# MCU.net
KiCad netlist of a schematic drawn in Altium Designer
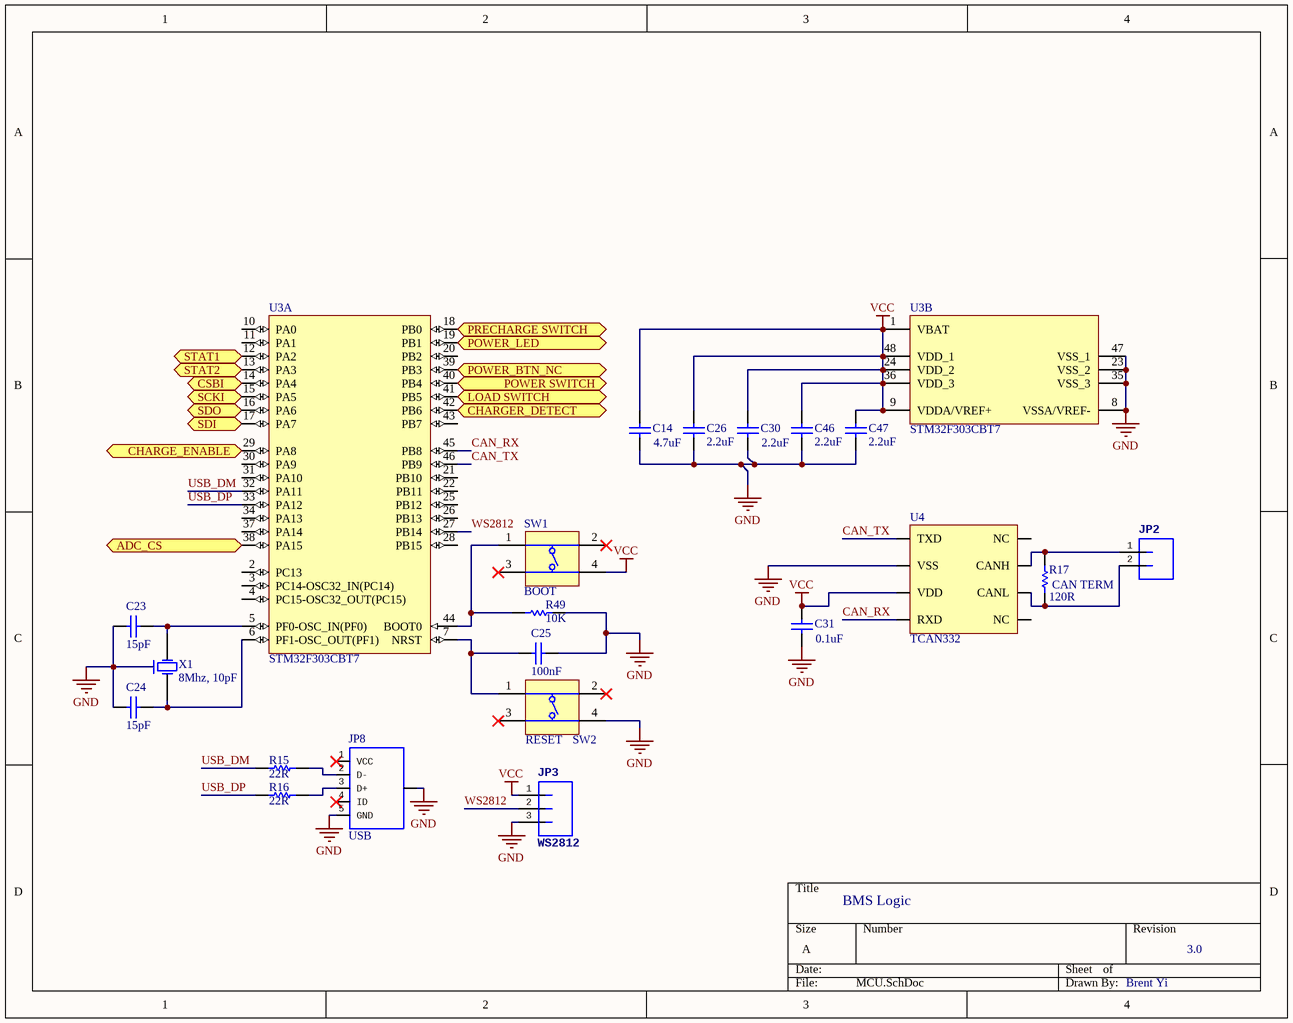
[diagram p0: MCU.SchDoc]

(export (version "E")
  (design (tool "Eeschema 10.0.6"))
  (components
    (comp (ref "C14")
      (value "4.7uF")
      (footprint "CAPC0603(1608)55_N")
      (description "CAP 2.2uF 16V Â±10% 0603 (1608 Metric) Thickness 0.55mm SMD")
      (fields (field (name "TOLERANCE") "Â±10%"))
      (libsource (lib "Altium Content Vault") (part "CMP-1035-02762-1"))
    )
    (comp (ref "C23")
      (value "15pF")
      (footprint "CAPC0603(1608)55_N")
      (description "CAP 2.2uF 16V Â±10% 0603 (1608 Metric) Thickness 0.55mm SMD")
      (fields (field (name "TOLERANCE") "Â±10%"))
      (libsource (lib "Altium Content Vault") (part "CMP-1035-02762-1"))
    )
    (comp (ref "C24")
      (value "15pF")
      (footprint "CAPC0603(1608)55_N")
      (description "CAP 2.2uF 16V Â±10% 0603 (1608 Metric) Thickness 0.55mm SMD")
      (fields (field (name "TOLERANCE") "Â±10%"))
      (libsource (lib "Altium Content Vault") (part "CMP-1035-02762-1"))
    )
    (comp (ref "C25")
      (value "100nF")
      (footprint "CAPC0603(1608)55_N")
      (description "CAP 2.2uF 16V Â±10% 0603 (1608 Metric) Thickness 0.55mm SMD")
      (fields (field (name "TOLERANCE") "Â±10%"))
      (libsource (lib "Altium Content Vault") (part "CMP-1035-02762-1"))
    )
    (comp (ref "C26")
      (value "2.2uF")
      (footprint "CAPC0603(1608)55_N")
      (description "CAP 2.2uF 16V Â±10% 0603 (1608 Metric) Thickness 0.55mm SMD")
      (fields (field (name "TOLERANCE") "Â±10%"))
      (libsource (lib "Altium Content Vault") (part "CMP-1035-02762-1"))
    )
    (comp (ref "C30")
      (value "2.2uF")
      (footprint "CAPC0603(1608)55_N")
      (description "CAP 2.2uF 16V Â±10% 0603 (1608 Metric) Thickness 0.55mm SMD")
      (fields (field (name "TOLERANCE") "Â±10%"))
      (libsource (lib "Altium Content Vault") (part "CMP-1035-02762-1"))
    )
    (comp (ref "C31")
      (value "0.1uF")
      (footprint "CAPC0603(1608)55_N")
      (description "CAP 2.2uF 16V Â±10% 0603 (1608 Metric) Thickness 0.55mm SMD")
      (fields (field (name "TOLERANCE") "Â±10%"))
      (libsource (lib "Altium Content Vault") (part "CMP-1035-02762-1"))
    )
    (comp (ref "C46")
      (value "2.2uF")
      (footprint "CAPC0603(1608)55_N")
      (description "CAP 2.2uF 16V Â±10% 0603 (1608 Metric) Thickness 0.55mm SMD")
      (fields (field (name "TOLERANCE") "Â±10%"))
      (libsource (lib "Altium Content Vault") (part "CMP-1035-02762-1"))
    )
    (comp (ref "C47")
      (value "2.2uF")
      (footprint "CAPC0603(1608)55_N")
      (description "CAP 2.2uF 16V Â±10% 0603 (1608 Metric) Thickness 0.55mm SMD")
      (fields (field (name "TOLERANCE") "Â±10%"))
      (libsource (lib "Altium Content Vault") (part "CMP-1035-02762-1"))
    )
    (comp (ref "JP2")
      (value "~")
      (footprint "JST-2-PTH-VERT")
      (libsource (lib "Components") (part "JST_2_VERT"))
    )
    (comp (ref "JP3")
      (value "WS2812")
      (footprint "JST-3-PTH-VERT")
      (libsource (lib "Components") (part "JST_3"))
    )
    (comp (ref "JP8")
      (value "USB")
      (footprint "USB-MICROB")
      (libsource (lib "Components") (part "USB_MICROB_PLUG-SMT"))
    )
    (comp (ref "R15")
      (value "22R")
      (footprint "RESC0603(1608)_N")
      (description "100R 0.1W 5% 0603 (1608 Metric)  SMD")
      (fields (field (name "TOLERANCE") "5 %") (field (name "POWER") "0.1 W"))
      (libsource (lib "Altium Content Vault") (part "CMP-1012-00050-1"))
    )
    (comp (ref "R16")
      (value "22R")
      (footprint "RESC0603(1608)_N")
      (description "100R 0.1W 5% 0603 (1608 Metric)  SMD")
      (fields (field (name "TOLERANCE") "5 %") (field (name "POWER") "0.1 W"))
      (libsource (lib "Altium Content Vault") (part "CMP-1012-00050-1"))
    )
    (comp (ref "R17")
      (value "CAN TERM")
      (footprint "RESC0603(1608)_N")
      (description "100R 0.1W 5% 0603 (1608 Metric)  SMD")
      (fields
        (field (name "TOLERANCE") "5 %")
        (field (name "ALTIUM_VALUE") "120R")
        (field (name "POWER") "0.1 W")
      )
      (libsource (lib "Altium Content Vault") (part "CMP-1012-00050-1"))
    )
    (comp (ref "R49")
      (value "10K")
      (footprint "RESC0603(1608)_N")
      (description "100R 0.1W 5% 0603 (1608 Metric)  SMD")
      (fields (field (name "TOLERANCE") "5 %") (field (name "POWER") "0.1 W"))
      (libsource (lib "Altium Content Vault") (part "CMP-1012-00050-1"))
    )
    (comp (ref "SW1")
      (value "BOOT")
      (footprint "SWITCH")
      (description "Switch, SPNO Push Button SMD")
      (fields (field (name "MANUFACTURER") "Diptronics") (field (name "PARTNUMBER") "DTSM-61NT/R"))
      (libsource (lib "altium-import") (part "root_0_DIPT-DTSM-6_"))
    )
    (comp (ref "SW2")
      (value "RESET")
      (footprint "SWITCH")
      (description "Switch, SPNO Push Button SMD")
      (fields (field (name "MANUFACTURER") "Diptronics") (field (name "PARTNUMBER") "DTSM-61NT/R"))
      (libsource (lib "altium-import") (part "root_0_DIPT-DTSM-6_"))
    )
    (comp (ref "U3")
      (value "STM32F303CBT7")
      (footprint "STM-LQFP48_L")
      (libsource (lib "Altium Content Vault") (part "MC-ARM-STM32F303-SQ48"))
    )
    (comp (ref "U4")
      (value "TCAN332")
      (footprint "SOT65P280X145-6N")
      (libsource (lib "Components") (part "TCAN332"))
    )
    (comp (ref "X1")
      (value "8Mhz, 10pF")
      (footprint "ABRA-ABM3B-4_V")
      (libsource (lib "Components") (part "ABRA-ABM3B-4"))
    )
  )
  (nets
    (net (code "1") (name "/ADC_CS") (class "Default")
      (node (ref "U3") (pin "38") (pinfunction "PA15_38") (pintype "bidirectional"))
    )
    (net (code "2") (name "/CAN_RX") (class "Default")
      (node (ref "U3") (pin "45") (pinfunction "PB8_45") (pintype "bidirectional"))
      (node (ref "U4") (pin "4") (pinfunction "RXD_4") (pintype "passive"))
    )
    (net (code "3") (name "/CAN_TX") (class "Default")
      (node (ref "U3") (pin "46") (pinfunction "PB9_46") (pintype "bidirectional"))
      (node (ref "U4") (pin "1") (pinfunction "TXD_1") (pintype "passive"))
    )
    (net (code "4") (name "/CHARGER_DETECT") (class "Default")
      (node (ref "U3") (pin "42") (pinfunction "PB6_42") (pintype "bidirectional"))
    )
    (net (code "5") (name "/CHARGE_ENABLE") (class "Default")
      (node (ref "U3") (pin "29") (pinfunction "PA8_29") (pintype "bidirectional"))
    )
    (net (code "6") (name "/CSBI") (class "Default")
      (node (ref "U3") (pin "14") (pinfunction "PA4_14") (pintype "bidirectional"))
    )
    (net (code "7") (name "/LOAD SWITCH") (class "Default")
      (node (ref "U3") (pin "41") (pinfunction "PB5_41") (pintype "bidirectional"))
    )
    (net (code "8") (name "/POWER SWITCH") (class "Default")
      (node (ref "U3") (pin "40") (pinfunction "PB4_40") (pintype "bidirectional"))
    )
    (net (code "9") (name "/POWER_BTN_NC") (class "Default")
      (node (ref "U3") (pin "39") (pinfunction "PB3_39") (pintype "bidirectional"))
    )
    (net (code "10") (name "/POWER_LED") (class "Default")
      (node (ref "U3") (pin "19") (pinfunction "PB1_19") (pintype "bidirectional"))
    )
    (net (code "11") (name "/PRECHARGE SWITCH") (class "Default")
      (node (ref "U3") (pin "18") (pinfunction "PB0_18") (pintype "bidirectional"))
    )
    (net (code "12") (name "/SCKI") (class "Default")
      (node (ref "U3") (pin "15") (pinfunction "PA5_15") (pintype "bidirectional"))
    )
    (net (code "13") (name "/SDI") (class "Default")
      (node (ref "U3") (pin "17") (pinfunction "PA7_17") (pintype "bidirectional"))
    )
    (net (code "14") (name "/SDO") (class "Default")
      (node (ref "U3") (pin "16") (pinfunction "PA6_16") (pintype "bidirectional"))
    )
    (net (code "15") (name "/STAT1") (class "Default")
      (node (ref "U3") (pin "12") (pinfunction "PA2_12") (pintype "bidirectional"))
    )
    (net (code "16") (name "/STAT2") (class "Default")
      (node (ref "U3") (pin "13") (pinfunction "PA3_13") (pintype "bidirectional"))
    )
    (net (code "17") (name "/USB_DM") (class "Default")
      (node (ref "R15") (pin "1") (pinfunction "1_1") (pintype "passive"))
      (node (ref "U3") (pin "32") (pinfunction "PA11_32") (pintype "bidirectional"))
    )
    (net (code "18") (name "/USB_DP") (class "Default")
      (node (ref "R16") (pin "1") (pinfunction "1_1") (pintype "passive"))
      (node (ref "U3") (pin "33") (pinfunction "PA12_33") (pintype "bidirectional"))
    )
    (net (code "19") (name "/WS2812") (class "Default")
      (node (ref "JP3") (pin "2") (pinfunction "2_2") (pintype "passive"))
      (node (ref "U3") (pin "27") (pinfunction "PB14_27") (pintype "bidirectional"))
    )
    (net (code "20") (name "GND") (class "Default")
      (node (ref "C14") (pin "1") (pinfunction "1_1") (pintype "passive"))
      (node (ref "C23") (pin "2") (pinfunction "2_2") (pintype "passive"))
      (node (ref "C24") (pin "2") (pinfunction "2_2") (pintype "passive"))
      (node (ref "C25") (pin "1") (pinfunction "1_1") (pintype "passive"))
      (node (ref "C26") (pin "1") (pinfunction "1_1") (pintype "passive"))
      (node (ref "C30") (pin "1") (pinfunction "1_1") (pintype "passive"))
      (node (ref "C31") (pin "1") (pinfunction "1_1") (pintype "passive"))
      (node (ref "C46") (pin "1") (pinfunction "1_1") (pintype "passive"))
      (node (ref "C47") (pin "1") (pinfunction "1_1") (pintype "passive"))
      (node (ref "JP3") (pin "3") (pinfunction "3_3") (pintype "passive"))
      (node (ref "JP8") (pin "5") (pinfunction "GND_5") (pintype "passive"))
      (node (ref "JP8") (pin "6") (pinfunction "SHIELD_6") (pintype "passive"))
      (node (ref "R49") (pin "2") (pinfunction "2_2") (pintype "passive"))
      (node (ref "SW2") (pin "4") (pinfunction "T3_4") (pintype "passive"))
      (node (ref "U3") (pin "23") (pinfunction "VSS_2_23") (pintype "power_in"))
      (node (ref "U3") (pin "35") (pinfunction "VSS_3_35") (pintype "power_in"))
      (node (ref "U3") (pin "47") (pinfunction "VSS_1_47") (pintype "power_in"))
      (node (ref "U3") (pin "8") (pinfunction "VSSA/VREF-_8") (pintype "power_in"))
      (node (ref "U4") (pin "2") (pinfunction "VSS_2") (pintype "passive"))
      (node (ref "X1") (pin "2") (pinfunction "2_2") (pintype "passive"))
    )
    (net (code "21") (name "Net-(JP8-D+)") (class "Default")
      (node (ref "JP8") (pin "3") (pinfunction "D+_3") (pintype "passive"))
      (node (ref "R16") (pin "2") (pinfunction "2_2") (pintype "passive"))
    )
    (net (code "22") (name "Net-(JP8-D-)") (class "Default")
      (node (ref "JP8") (pin "2") (pinfunction "D-_2") (pintype "passive"))
      (node (ref "R15") (pin "2") (pinfunction "2_2") (pintype "passive"))
    )
    (net (code "23") (name "Net-(SW1-T1)") (class "Default")
      (node (ref "R49") (pin "1") (pinfunction "1_1") (pintype "passive"))
      (node (ref "SW1") (pin "1") (pinfunction "T1_1") (pintype "passive"))
      (node (ref "U3") (pin "44") (pinfunction "BOOT0_44") (pintype "input"))
    )
    (net (code "24") (name "Net-(SW2-T1)") (class "Default")
      (node (ref "C25") (pin "2") (pinfunction "2_2") (pintype "passive"))
      (node (ref "SW2") (pin "1") (pinfunction "T1_1") (pintype "passive"))
      (node (ref "U3") (pin "7") (pinfunction "NRST_7") (pintype "bidirectional"))
    )
    (net (code "25") (name "Net-(U3A-PF0-OSC_IN(PF0))") (class "Default")
      (node (ref "C23") (pin "1") (pinfunction "1_1") (pintype "passive"))
      (node (ref "U3") (pin "5") (pinfunction "PF0-OSC_IN(PF0)_5") (pintype "bidirectional"))
      (node (ref "X1") (pin "1") (pinfunction "X1_1") (pintype "passive"))
    )
    (net (code "26") (name "Net-(U3A-PF1-OSC_OUT(PF1))") (class "Default")
      (node (ref "C24") (pin "1") (pinfunction "1_1") (pintype "passive"))
      (node (ref "U3") (pin "6") (pinfunction "PF1-OSC_OUT(PF1)_6") (pintype "bidirectional"))
      (node (ref "X1") (pin "3") (pinfunction "X2_3") (pintype "passive"))
    )
    (net (code "27") (name "Net-(U4-CANH)") (class "Default")
      (node (ref "JP2") (pin "1") (pinfunction "1_1") (pintype "passive"))
      (node (ref "R17") (pin "2") (pinfunction "2_2") (pintype "passive"))
      (node (ref "U4") (pin "7") (pinfunction "CANH_7") (pintype "passive"))
    )
    (net (code "28") (name "Net-(U4-CANL)") (class "Default")
      (node (ref "JP2") (pin "2") (pinfunction "2_2") (pintype "passive"))
      (node (ref "R17") (pin "1") (pinfunction "1_1") (pintype "passive"))
      (node (ref "U4") (pin "6") (pinfunction "CANL_6") (pintype "passive"))
    )
    (net (code "29") (name "VCC") (class "Default")
      (node (ref "C14") (pin "2") (pinfunction "2_2") (pintype "passive"))
      (node (ref "C26") (pin "2") (pinfunction "2_2") (pintype "passive"))
      (node (ref "C30") (pin "2") (pinfunction "2_2") (pintype "passive"))
      (node (ref "C31") (pin "2") (pinfunction "2_2") (pintype "passive"))
      (node (ref "C46") (pin "2") (pinfunction "2_2") (pintype "passive"))
      (node (ref "C47") (pin "2") (pinfunction "2_2") (pintype "passive"))
      (node (ref "JP3") (pin "1") (pinfunction "1_1") (pintype "passive"))
      (node (ref "SW1") (pin "4") (pinfunction "T3_4") (pintype "passive"))
      (node (ref "U3") (pin "1") (pinfunction "VBAT_1") (pintype "power_in"))
      (node (ref "U3") (pin "24") (pinfunction "VDD_2_24") (pintype "power_in"))
      (node (ref "U3") (pin "36") (pinfunction "VDD_3_36") (pintype "power_in"))
      (node (ref "U3") (pin "48") (pinfunction "VDD_1_48") (pintype "power_in"))
      (node (ref "U3") (pin "9") (pinfunction "VDDA/VREF+_9") (pintype "power_in"))
      (node (ref "U4") (pin "3") (pinfunction "VDD_3") (pintype "passive"))
    )
    (net (code "30") (name "unconnected-(JP8-ID-Pad4)") (class "Default")
      (node (ref "JP8") (pin "4") (pinfunction "ID_4") (pintype "passive+no_connect"))
    )
    (net (code "31") (name "unconnected-(JP8-VCC-Pad1)") (class "Default")
      (node (ref "JP8") (pin "1") (pinfunction "VCC_1") (pintype "passive+no_connect"))
    )
    (net (code "32") (name "unconnected-(SW1-T2-Pad2)") (class "Default")
      (node (ref "SW1") (pin "2") (pinfunction "T2_2") (pintype "passive+no_connect"))
    )
    (net (code "33") (name "unconnected-(SW1-T3-Pad3)") (class "Default")
      (node (ref "SW1") (pin "3") (pinfunction "T3_3") (pintype "passive+no_connect"))
    )
    (net (code "34") (name "unconnected-(SW2-T2-Pad2)") (class "Default")
      (node (ref "SW2") (pin "2") (pinfunction "T2_2") (pintype "passive+no_connect"))
    )
    (net (code "35") (name "unconnected-(SW2-T3-Pad3)") (class "Default")
      (node (ref "SW2") (pin "3") (pinfunction "T3_3") (pintype "passive+no_connect"))
    )
    (net (code "36") (name "unconnected-(U3A-PA0-Pad10)") (class "Default")
      (node (ref "U3") (pin "10") (pinfunction "PA0_10") (pintype "bidirectional"))
    )
    (net (code "37") (name "unconnected-(U3A-PA1-Pad11)") (class "Default")
      (node (ref "U3") (pin "11") (pinfunction "PA1_11") (pintype "bidirectional"))
    )
    (net (code "38") (name "unconnected-(U3A-PA9-Pad30)") (class "Default")
      (node (ref "U3") (pin "30") (pinfunction "PA9_30") (pintype "bidirectional"))
    )
    (net (code "39") (name "unconnected-(U3A-PA10-Pad31)") (class "Default")
      (node (ref "U3") (pin "31") (pinfunction "PA10_31") (pintype "bidirectional"))
    )
    (net (code "40") (name "unconnected-(U3A-PA13-Pad34)") (class "Default")
      (node (ref "U3") (pin "34") (pinfunction "PA13_34") (pintype "bidirectional"))
    )
    (net (code "41") (name "unconnected-(U3A-PA14-Pad37)") (class "Default")
      (node (ref "U3") (pin "37") (pinfunction "PA14_37") (pintype "bidirectional"))
    )
    (net (code "42") (name "unconnected-(U3A-PB2-Pad20)") (class "Default")
      (node (ref "U3") (pin "20") (pinfunction "PB2_20") (pintype "bidirectional"))
    )
    (net (code "43") (name "unconnected-(U3A-PB7-Pad43)") (class "Default")
      (node (ref "U3") (pin "43") (pinfunction "PB7_43") (pintype "bidirectional"))
    )
    (net (code "44") (name "unconnected-(U3A-PB10-Pad21)") (class "Default")
      (node (ref "U3") (pin "21") (pinfunction "PB10_21") (pintype "bidirectional"))
    )
    (net (code "45") (name "unconnected-(U3A-PB11-Pad22)") (class "Default")
      (node (ref "U3") (pin "22") (pinfunction "PB11_22") (pintype "bidirectional"))
    )
    (net (code "46") (name "unconnected-(U3A-PB12-Pad25)") (class "Default")
      (node (ref "U3") (pin "25") (pinfunction "PB12_25") (pintype "bidirectional"))
    )
    (net (code "47") (name "unconnected-(U3A-PB13-Pad26)") (class "Default")
      (node (ref "U3") (pin "26") (pinfunction "PB13_26") (pintype "bidirectional"))
    )
    (net (code "48") (name "unconnected-(U3A-PB15-Pad28)") (class "Default")
      (node (ref "U3") (pin "28") (pinfunction "PB15_28") (pintype "bidirectional"))
    )
    (net (code "49") (name "unconnected-(U3A-PC13-Pad2)") (class "Default")
      (node (ref "U3") (pin "2") (pinfunction "PC13_2") (pintype "bidirectional"))
    )
    (net (code "50") (name "unconnected-(U3A-PC14-OSC32_IN(PC14)-Pad3)") (class "Default")
      (node (ref "U3") (pin "3") (pinfunction "PC14-OSC32_IN(PC14)_3") (pintype "bidirectional"))
    )
    (net (code "51") (name "unconnected-(U3A-PC15-OSC32_OUT(PC15)-Pad4)") (class "Default")
      (node (ref "U3") (pin "4") (pinfunction "PC15-OSC32_OUT(PC15)_4") (pintype "bidirectional"))
    )
    (net (code "52") (name "unconnected-(U4-NC-Pad5)") (class "Default")
      (node (ref "U4") (pin "5") (pinfunction "NC_5") (pintype "passive"))
    )
    (net (code "53") (name "unconnected-(U4-NC-Pad8)") (class "Default")
      (node (ref "U4") (pin "8") (pinfunction "NC_8") (pintype "passive"))
    )
  )
)
